# Cooling.net
KiCad netlist of a schematic drawn in Altium Designer
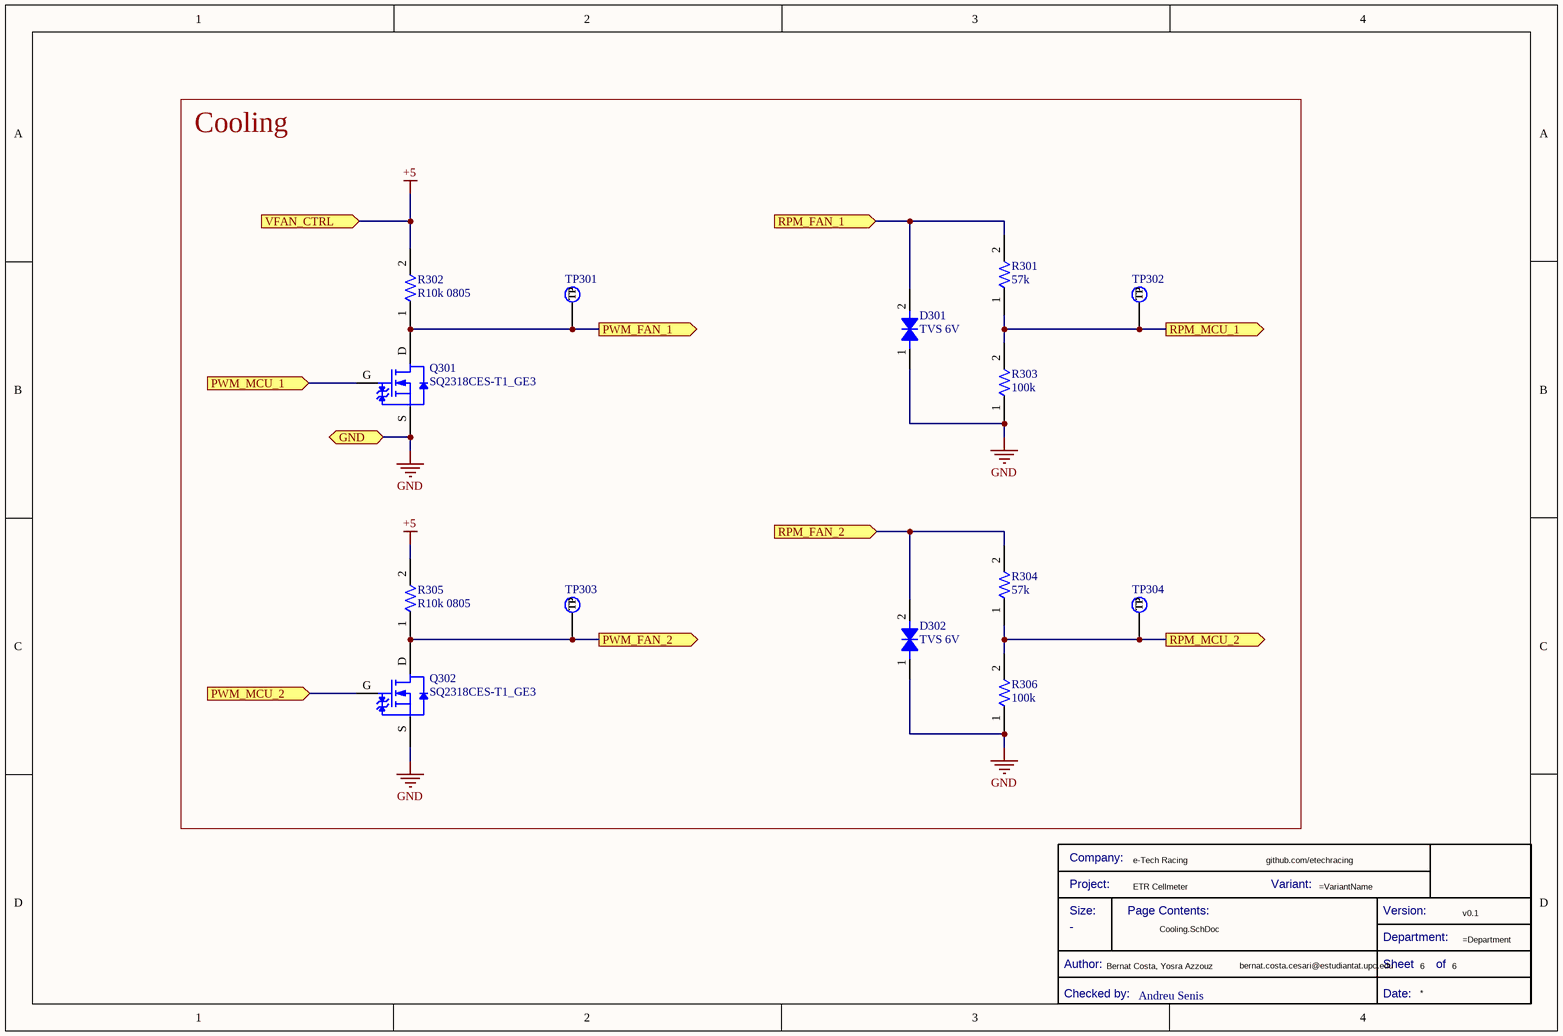
[diagram p0: Cooling.SchDoc]

(export (version "E")
  (design (tool "Eeschema 10.0.6"))
  (components
    (comp (ref "D301")
      (value "TVS 6V")
      (footprint "DTVS-DO-214AC")
      (description "TVS diode [Würth Elektronik] 824501600 TVS diode")
      (fields
        (field (name "MANUFACTURER") "Wurth Electronics")
        (field (name "MANUFACTURER PART NUMBER") "824501600")
        (field (name ".CREATOR") "DO")
      )
      (libsource (lib "EMEA- E-Tech Racing- I'Escola d'Enginyeria de Barcelona Est") (part "DTVS-BD-30k-SOD323"))
    )
    (comp (ref "D302")
      (value "TVS 6V")
      (footprint "DTVS-DO-214AC")
      (description "TVS diode [Würth Elektronik] 824501600 TVS diode")
      (fields
        (field (name "MANUFACTURER") "Wurth Electronics")
        (field (name "MANUFACTURER PART NUMBER") "824501600")
        (field (name ".CREATOR") "DO")
      )
      (libsource (lib "EMEA- E-Tech Racing- I'Escola d'Enginyeria de Barcelona Est") (part "DTVS-BD-30k-SOD323"))
    )
    (comp (ref "Q301")
      (value "SQ2318CES-T1_GE3")
      (footprint "SOT95P245X110-3N")
      (description "Mosfet, N-channel, 40V, 7A, SOT-23 Rohs Compliant: Yes")
      (libsource (lib "EMEA- E-Tech Racing- I'Escola d'Enginyeria de Barcelona Est") (part "TRT-NCH-3/35-CPH"))
    )
    (comp (ref "Q302")
      (value "SQ2318CES-T1_GE3")
      (footprint "SOT95P245X110-3N")
      (description "Mosfet, N-channel, 40V, 7A, SOT-23 Rohs Compliant: Yes")
      (libsource (lib "EMEA- E-Tech Racing- I'Escola d'Enginyeria de Barcelona Est") (part "TRT-NCH-3/35-CPH"))
    )
    (comp (ref "R301")
      (value "57k")
      (footprint "0805")
      (fields
        (field (name "POWER") "125mW")
        (field (name "TOLERANCE") "1%")
        (field (name "Comment") "R51k_0805")
      )
      (libsource (lib "EMEA- E-Tech Racing- I'Escola d'Enginyeria de Barcelona Est") (part "R9.09K-1206FTK"))
    )
    (comp (ref "R302")
      (value "R10k 0805")
      (footprint "R0805FTK")
      (fields (field (name "TOLERANCE") "5%") (field (name ".CREATOR") "DR"))
      (libsource (lib "EMEA- E-Tech Racing- I'Escola d'Enginyeria de Barcelona Est") (part "R9.09K-1206FTK"))
    )
    (comp (ref "R303")
      (value "100k")
      (footprint "RESC2013X70X40NL20T20")
      (fields
        (field (name "POWER") "125mW")
        (field (name "TOLERANCE") "5%")
        (field (name "Comment") "R100k-0805")
      )
      (libsource (lib "EMEA- E-Tech Racing- I'Escola d'Enginyeria de Barcelona Est") (part "R9.09K-1206FTK"))
    )
    (comp (ref "R304")
      (value "57k")
      (footprint "0805")
      (fields
        (field (name "POWER") "125mW")
        (field (name "TOLERANCE") "1%")
        (field (name "Comment") "R51k_0805")
      )
      (libsource (lib "EMEA- E-Tech Racing- I'Escola d'Enginyeria de Barcelona Est") (part "R9.09K-1206FTK"))
    )
    (comp (ref "R305")
      (value "R10k 0805")
      (footprint "R0805FTK")
      (fields (field (name "TOLERANCE") "5%") (field (name ".CREATOR") "DR"))
      (libsource (lib "EMEA- E-Tech Racing- I'Escola d'Enginyeria de Barcelona Est") (part "R9.09K-1206FTK"))
    )
    (comp (ref "R306")
      (value "100k")
      (footprint "RESC2013X70X40NL20T20")
      (fields
        (field (name "POWER") "125mW")
        (field (name "TOLERANCE") "5%")
        (field (name "Comment") "R100k-0805")
      )
      (libsource (lib "EMEA- E-Tech Racing- I'Escola d'Enginyeria de Barcelona Est") (part "R9.09K-1206FTK"))
    )
    (comp (ref "TP301")
      (value "TestPoint")
      (footprint "TestPoint")
      (description "Test Point 1x1 mm")
      (fields (field (name ".SCHCHECK") "GP") (field (name ".CREATOR") "GP") (field (name ".PCBCHECK") "GP"))
      (libsource (lib "EMEA- E-Tech Racing- I'Escola d'Enginyeria de Barcelona Est") (part "TestPoint"))
    )
    (comp (ref "TP302")
      (value "TestPoint")
      (footprint "TestPoint")
      (description "Test Point 1x1 mm")
      (fields (field (name ".SCHCHECK") "GP") (field (name ".CREATOR") "GP") (field (name ".PCBCHECK") "GP"))
      (libsource (lib "EMEA- E-Tech Racing- I'Escola d'Enginyeria de Barcelona Est") (part "TestPoint"))
    )
    (comp (ref "TP303")
      (value "TestPoint")
      (footprint "TestPoint")
      (description "Test Point 1x1 mm")
      (fields (field (name ".SCHCHECK") "GP") (field (name ".CREATOR") "GP") (field (name ".PCBCHECK") "GP"))
      (libsource (lib "EMEA- E-Tech Racing- I'Escola d'Enginyeria de Barcelona Est") (part "TestPoint"))
    )
    (comp (ref "TP304")
      (value "TestPoint")
      (footprint "TestPoint")
      (description "Test Point 1x1 mm")
      (fields (field (name ".SCHCHECK") "GP") (field (name ".CREATOR") "GP") (field (name ".PCBCHECK") "GP"))
      (libsource (lib "EMEA- E-Tech Racing- I'Escola d'Enginyeria de Barcelona Est") (part "TestPoint"))
    )
  )
  (nets
    (net (code "1") (name "+5") (class "Default")
      (node (ref "R302") (pin "2") (pinfunction "2_2") (pintype "passive"))
      (node (ref "R305") (pin "2") (pinfunction "2_2") (pintype "passive"))
    )
    (net (code "2") (name "/PWM_FAN_1") (class "Default")
      (node (ref "Q301") (pin "D") (pinfunction "D_D") (pintype "passive"))
      (node (ref "R302") (pin "1") (pinfunction "1_1") (pintype "passive"))
      (node (ref "TP301") (pin "1") (pinfunction "TP_1") (pintype "passive"))
    )
    (net (code "3") (name "/PWM_FAN_2") (class "Default")
      (node (ref "Q302") (pin "D") (pinfunction "D_D") (pintype "passive"))
      (node (ref "R305") (pin "1") (pinfunction "1_1") (pintype "passive"))
      (node (ref "TP303") (pin "1") (pinfunction "TP_1") (pintype "passive"))
    )
    (net (code "4") (name "/PWM_MCU_1") (class "Default")
      (node (ref "Q301") (pin "G") (pinfunction "G_G") (pintype "passive"))
    )
    (net (code "5") (name "/PWM_MCU_2") (class "Default")
      (node (ref "Q302") (pin "G") (pinfunction "G_G") (pintype "passive"))
    )
    (net (code "6") (name "/RPM_FAN_1") (class "Default")
      (node (ref "D301") (pin "2") (pinfunction "2_2") (pintype "passive"))
      (node (ref "R301") (pin "2") (pinfunction "2_2") (pintype "passive"))
    )
    (net (code "7") (name "/RPM_FAN_2") (class "Default")
      (node (ref "D302") (pin "2") (pinfunction "2_2") (pintype "passive"))
      (node (ref "R304") (pin "2") (pinfunction "2_2") (pintype "passive"))
    )
    (net (code "8") (name "/RPM_MCU_1") (class "Default")
      (node (ref "R301") (pin "1") (pinfunction "1_1") (pintype "passive"))
      (node (ref "R303") (pin "2") (pinfunction "2_2") (pintype "passive"))
      (node (ref "TP302") (pin "1") (pinfunction "TP_1") (pintype "passive"))
    )
    (net (code "9") (name "/RPM_MCU_2") (class "Default")
      (node (ref "R304") (pin "1") (pinfunction "1_1") (pintype "passive"))
      (node (ref "R306") (pin "2") (pinfunction "2_2") (pintype "passive"))
      (node (ref "TP304") (pin "1") (pinfunction "TP_1") (pintype "passive"))
    )
    (net (code "10") (name "GND") (class "Default")
      (node (ref "D301") (pin "1") (pinfunction "1_1") (pintype "passive"))
      (node (ref "D302") (pin "1") (pinfunction "1_1") (pintype "passive"))
      (node (ref "Q301") (pin "S") (pinfunction "S_S") (pintype "passive"))
      (node (ref "Q302") (pin "S") (pinfunction "S_S") (pintype "passive"))
      (node (ref "R303") (pin "1") (pinfunction "1_1") (pintype "passive"))
      (node (ref "R306") (pin "1") (pinfunction "1_1") (pintype "passive"))
    )
  )
)
